# Inputs.net
KiCad netlist of a schematic drawn in Altium Designer
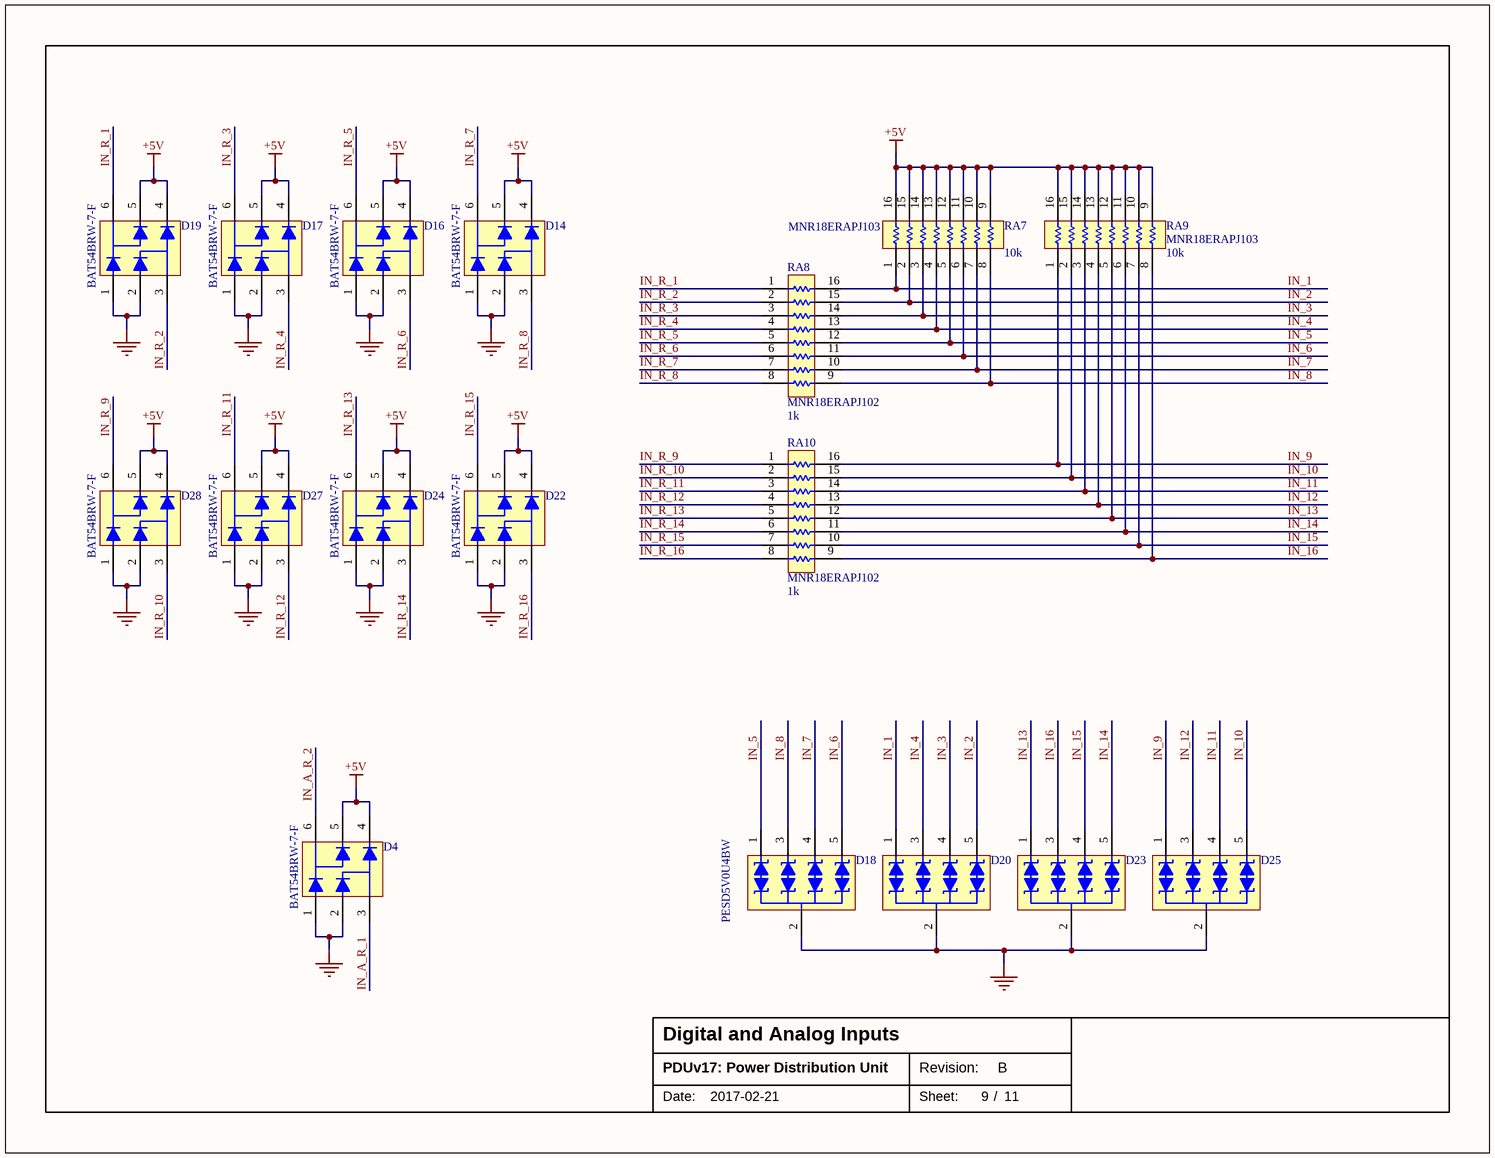
[diagram p0: Inputs.SchDoc]

(export (version "E")
  (design (tool "Eeschema 10.0.6"))
  (components
    (comp (ref "D4")
      (value "BAT54BRW-7-F")
      (footprint "SOT65P210X110-6N")
      (libsource (lib "PDU-UV17") (part "BAT54BRW-7-F"))
    )
    (comp (ref "D14")
      (value "BAT54BRW-7-F")
      (footprint "SOT65P210X110-6N")
      (libsource (lib "PDU-UV17") (part "BAT54BRW-7-F"))
    )
    (comp (ref "D16")
      (value "BAT54BRW-7-F")
      (footprint "SOT65P210X110-6N")
      (libsource (lib "PDU-UV17") (part "BAT54BRW-7-F"))
    )
    (comp (ref "D17")
      (value "BAT54BRW-7-F")
      (footprint "SOT65P210X110-6N")
      (libsource (lib "PDU-UV17") (part "BAT54BRW-7-F"))
    )
    (comp (ref "D18")
      (value "PESD5V0U4BW")
      (footprint "SOTFL50P160X60-5N")
      (libsource (lib "PDU-UV17") (part "PESD5V0U4BW"))
    )
    (comp (ref "D19")
      (value "BAT54BRW-7-F")
      (footprint "SOT65P210X110-6N")
      (libsource (lib "PDU-UV17") (part "BAT54BRW-7-F"))
    )
    (comp (ref "D20")
      (value "PESD5V0U4BW")
      (footprint "SOTFL50P160X60-5N")
      (libsource (lib "PDU-UV17") (part "PESD5V0U4BW"))
    )
    (comp (ref "D22")
      (value "BAT54BRW-7-F")
      (footprint "SOT65P210X110-6N")
      (libsource (lib "PDU-UV17") (part "BAT54BRW-7-F"))
    )
    (comp (ref "D23")
      (value "PESD5V0U4BW")
      (footprint "SOTFL50P160X60-5N")
      (libsource (lib "PDU-UV17") (part "PESD5V0U4BW"))
    )
    (comp (ref "D24")
      (value "BAT54BRW-7-F")
      (footprint "SOT65P210X110-6N")
      (libsource (lib "PDU-UV17") (part "BAT54BRW-7-F"))
    )
    (comp (ref "D25")
      (value "PESD5V0U4BW")
      (footprint "SOTFL50P160X60-5N")
      (libsource (lib "PDU-UV17") (part "PESD5V0U4BW"))
    )
    (comp (ref "D27")
      (value "BAT54BRW-7-F")
      (footprint "SOT65P210X110-6N")
      (libsource (lib "PDU-UV17") (part "BAT54BRW-7-F"))
    )
    (comp (ref "D28")
      (value "BAT54BRW-7-F")
      (footprint "SOT65P210X110-6N")
      (libsource (lib "PDU-UV17") (part "BAT54BRW-7-F"))
    )
    (comp (ref "RA7")
      (value "MNR18ERAPJ103")
      (footprint "CAC-50P379X150-16N")
      (fields (field (name "ALTIUM_VALUE") "10k"))
      (libsource (lib "PDU-UV17") (part "MNR18ERAPJ103"))
    )
    (comp (ref "RA8")
      (value "MNR18ERAPJ102")
      (footprint "CAC-50P379X150-16N")
      (fields (field (name "ALTIUM_VALUE") "1k"))
      (libsource (lib "PDU-UV17") (part "MNR18ERAPJ102"))
    )
    (comp (ref "RA9")
      (value "MNR18ERAPJ103")
      (footprint "CAC-50P379X150-16N")
      (fields (field (name "ALTIUM_VALUE") "10k"))
      (libsource (lib "PDU-UV17") (part "MNR18ERAPJ103"))
    )
    (comp (ref "RA10")
      (value "MNR18ERAPJ102")
      (footprint "CAC-50P379X150-16N")
      (fields (field (name "ALTIUM_VALUE") "1k"))
      (libsource (lib "PDU-UV17") (part "MNR18ERAPJ102"))
    )
  )
  (nets
    (net (code "1") (name "+5V") (class "Default")
      (node (ref "D14") (pin "4") (pinfunction "4_4") (pintype "passive"))
      (node (ref "D14") (pin "5") (pinfunction "5_5") (pintype "passive"))
      (node (ref "D16") (pin "4") (pinfunction "4_4") (pintype "passive"))
      (node (ref "D16") (pin "5") (pinfunction "5_5") (pintype "passive"))
      (node (ref "D17") (pin "4") (pinfunction "4_4") (pintype "passive"))
      (node (ref "D17") (pin "5") (pinfunction "5_5") (pintype "passive"))
      (node (ref "D19") (pin "4") (pinfunction "4_4") (pintype "passive"))
      (node (ref "D19") (pin "5") (pinfunction "5_5") (pintype "passive"))
      (node (ref "D22") (pin "4") (pinfunction "4_4") (pintype "passive"))
      (node (ref "D22") (pin "5") (pinfunction "5_5") (pintype "passive"))
      (node (ref "D24") (pin "4") (pinfunction "4_4") (pintype "passive"))
      (node (ref "D24") (pin "5") (pinfunction "5_5") (pintype "passive"))
      (node (ref "D27") (pin "4") (pinfunction "4_4") (pintype "passive"))
      (node (ref "D27") (pin "5") (pinfunction "5_5") (pintype "passive"))
      (node (ref "D28") (pin "4") (pinfunction "4_4") (pintype "passive"))
      (node (ref "D28") (pin "5") (pinfunction "5_5") (pintype "passive"))
      (node (ref "D4") (pin "4") (pinfunction "4_4") (pintype "passive"))
      (node (ref "D4") (pin "5") (pinfunction "5_5") (pintype "passive"))
      (node (ref "RA7") (pin "10") (pinfunction "10_10") (pintype "passive"))
      (node (ref "RA7") (pin "11") (pinfunction "11_11") (pintype "passive"))
      (node (ref "RA7") (pin "12") (pinfunction "12_12") (pintype "passive"))
      (node (ref "RA7") (pin "13") (pinfunction "13_13") (pintype "passive"))
      (node (ref "RA7") (pin "14") (pinfunction "14_14") (pintype "passive"))
      (node (ref "RA7") (pin "15") (pinfunction "15_15") (pintype "passive"))
      (node (ref "RA7") (pin "16") (pinfunction "16_16") (pintype "passive"))
      (node (ref "RA7") (pin "9") (pinfunction "9_9") (pintype "passive"))
      (node (ref "RA9") (pin "10") (pinfunction "10_10") (pintype "passive"))
      (node (ref "RA9") (pin "11") (pinfunction "11_11") (pintype "passive"))
      (node (ref "RA9") (pin "12") (pinfunction "12_12") (pintype "passive"))
      (node (ref "RA9") (pin "13") (pinfunction "13_13") (pintype "passive"))
      (node (ref "RA9") (pin "14") (pinfunction "14_14") (pintype "passive"))
      (node (ref "RA9") (pin "15") (pinfunction "15_15") (pintype "passive"))
      (node (ref "RA9") (pin "16") (pinfunction "16_16") (pintype "passive"))
      (node (ref "RA9") (pin "9") (pinfunction "9_9") (pintype "passive"))
    )
    (net (code "2") (name "/IN_1") (class "Default")
      (node (ref "D20") (pin "1") (pinfunction "1_1") (pintype "passive"))
      (node (ref "RA7") (pin "1") (pinfunction "1_1") (pintype "passive"))
      (node (ref "RA8") (pin "16") (pinfunction "16_16") (pintype "passive"))
    )
    (net (code "3") (name "/IN_2") (class "Default")
      (node (ref "D20") (pin "5") (pinfunction "5_5") (pintype "passive"))
      (node (ref "RA7") (pin "2") (pinfunction "2_2") (pintype "passive"))
      (node (ref "RA8") (pin "15") (pinfunction "15_15") (pintype "passive"))
    )
    (net (code "4") (name "/IN_3") (class "Default")
      (node (ref "D20") (pin "4") (pinfunction "4_4") (pintype "passive"))
      (node (ref "RA7") (pin "3") (pinfunction "3_3") (pintype "passive"))
      (node (ref "RA8") (pin "14") (pinfunction "14_14") (pintype "passive"))
    )
    (net (code "5") (name "/IN_4") (class "Default")
      (node (ref "D20") (pin "3") (pinfunction "3_3") (pintype "passive"))
      (node (ref "RA7") (pin "4") (pinfunction "4_4") (pintype "passive"))
      (node (ref "RA8") (pin "13") (pinfunction "13_13") (pintype "passive"))
    )
    (net (code "6") (name "/IN_5") (class "Default")
      (node (ref "D18") (pin "1") (pinfunction "1_1") (pintype "passive"))
      (node (ref "RA7") (pin "5") (pinfunction "5_5") (pintype "passive"))
      (node (ref "RA8") (pin "12") (pinfunction "12_12") (pintype "passive"))
    )
    (net (code "7") (name "/IN_6") (class "Default")
      (node (ref "D18") (pin "5") (pinfunction "5_5") (pintype "passive"))
      (node (ref "RA7") (pin "6") (pinfunction "6_6") (pintype "passive"))
      (node (ref "RA8") (pin "11") (pinfunction "11_11") (pintype "passive"))
    )
    (net (code "8") (name "/IN_7") (class "Default")
      (node (ref "D18") (pin "4") (pinfunction "4_4") (pintype "passive"))
      (node (ref "RA7") (pin "7") (pinfunction "7_7") (pintype "passive"))
      (node (ref "RA8") (pin "10") (pinfunction "10_10") (pintype "passive"))
    )
    (net (code "9") (name "/IN_8") (class "Default")
      (node (ref "D18") (pin "3") (pinfunction "3_3") (pintype "passive"))
      (node (ref "RA7") (pin "8") (pinfunction "8_8") (pintype "passive"))
      (node (ref "RA8") (pin "9") (pinfunction "9_9") (pintype "passive"))
    )
    (net (code "10") (name "/IN_9") (class "Default")
      (node (ref "D25") (pin "1") (pinfunction "1_1") (pintype "passive"))
      (node (ref "RA10") (pin "16") (pinfunction "16_16") (pintype "passive"))
      (node (ref "RA9") (pin "1") (pinfunction "1_1") (pintype "passive"))
    )
    (net (code "11") (name "/IN_10") (class "Default")
      (node (ref "D25") (pin "5") (pinfunction "5_5") (pintype "passive"))
      (node (ref "RA10") (pin "15") (pinfunction "15_15") (pintype "passive"))
      (node (ref "RA9") (pin "2") (pinfunction "2_2") (pintype "passive"))
    )
    (net (code "12") (name "/IN_11") (class "Default")
      (node (ref "D25") (pin "4") (pinfunction "4_4") (pintype "passive"))
      (node (ref "RA10") (pin "14") (pinfunction "14_14") (pintype "passive"))
      (node (ref "RA9") (pin "3") (pinfunction "3_3") (pintype "passive"))
    )
    (net (code "13") (name "/IN_12") (class "Default")
      (node (ref "D25") (pin "3") (pinfunction "3_3") (pintype "passive"))
      (node (ref "RA10") (pin "13") (pinfunction "13_13") (pintype "passive"))
      (node (ref "RA9") (pin "4") (pinfunction "4_4") (pintype "passive"))
    )
    (net (code "14") (name "/IN_13") (class "Default")
      (node (ref "D23") (pin "1") (pinfunction "1_1") (pintype "passive"))
      (node (ref "RA10") (pin "12") (pinfunction "12_12") (pintype "passive"))
      (node (ref "RA9") (pin "5") (pinfunction "5_5") (pintype "passive"))
    )
    (net (code "15") (name "/IN_14") (class "Default")
      (node (ref "D23") (pin "5") (pinfunction "5_5") (pintype "passive"))
      (node (ref "RA10") (pin "11") (pinfunction "11_11") (pintype "passive"))
      (node (ref "RA9") (pin "6") (pinfunction "6_6") (pintype "passive"))
    )
    (net (code "16") (name "/IN_15") (class "Default")
      (node (ref "D23") (pin "4") (pinfunction "4_4") (pintype "passive"))
      (node (ref "RA10") (pin "10") (pinfunction "10_10") (pintype "passive"))
      (node (ref "RA9") (pin "7") (pinfunction "7_7") (pintype "passive"))
    )
    (net (code "17") (name "/IN_16") (class "Default")
      (node (ref "D23") (pin "3") (pinfunction "3_3") (pintype "passive"))
      (node (ref "RA10") (pin "9") (pinfunction "9_9") (pintype "passive"))
      (node (ref "RA9") (pin "8") (pinfunction "8_8") (pintype "passive"))
    )
    (net (code "18") (name "/IN_A_R_1") (class "Default")
      (node (ref "D4") (pin "3") (pinfunction "3_3") (pintype "passive"))
    )
    (net (code "19") (name "/IN_A_R_2") (class "Default")
      (node (ref "D4") (pin "6") (pinfunction "6_6") (pintype "passive"))
    )
    (net (code "20") (name "/IN_R_1") (class "Default")
      (node (ref "D19") (pin "6") (pinfunction "6_6") (pintype "passive"))
      (node (ref "RA8") (pin "1") (pinfunction "1_1") (pintype "passive"))
    )
    (net (code "21") (name "/IN_R_2") (class "Default")
      (node (ref "D19") (pin "3") (pinfunction "3_3") (pintype "passive"))
      (node (ref "RA8") (pin "2") (pinfunction "2_2") (pintype "passive"))
    )
    (net (code "22") (name "/IN_R_3") (class "Default")
      (node (ref "D17") (pin "6") (pinfunction "6_6") (pintype "passive"))
      (node (ref "RA8") (pin "3") (pinfunction "3_3") (pintype "passive"))
    )
    (net (code "23") (name "/IN_R_4") (class "Default")
      (node (ref "D17") (pin "3") (pinfunction "3_3") (pintype "passive"))
      (node (ref "RA8") (pin "4") (pinfunction "4_4") (pintype "passive"))
    )
    (net (code "24") (name "/IN_R_5") (class "Default")
      (node (ref "D16") (pin "6") (pinfunction "6_6") (pintype "passive"))
      (node (ref "RA8") (pin "5") (pinfunction "5_5") (pintype "passive"))
    )
    (net (code "25") (name "/IN_R_6") (class "Default")
      (node (ref "D16") (pin "3") (pinfunction "3_3") (pintype "passive"))
      (node (ref "RA8") (pin "6") (pinfunction "6_6") (pintype "passive"))
    )
    (net (code "26") (name "/IN_R_7") (class "Default")
      (node (ref "D14") (pin "6") (pinfunction "6_6") (pintype "passive"))
      (node (ref "RA8") (pin "7") (pinfunction "7_7") (pintype "passive"))
    )
    (net (code "27") (name "/IN_R_8") (class "Default")
      (node (ref "D14") (pin "3") (pinfunction "3_3") (pintype "passive"))
      (node (ref "RA8") (pin "8") (pinfunction "8_8") (pintype "passive"))
    )
    (net (code "28") (name "/IN_R_9") (class "Default")
      (node (ref "D28") (pin "6") (pinfunction "6_6") (pintype "passive"))
      (node (ref "RA10") (pin "1") (pinfunction "1_1") (pintype "passive"))
    )
    (net (code "29") (name "/IN_R_10") (class "Default")
      (node (ref "D28") (pin "3") (pinfunction "3_3") (pintype "passive"))
      (node (ref "RA10") (pin "2") (pinfunction "2_2") (pintype "passive"))
    )
    (net (code "30") (name "/IN_R_11") (class "Default")
      (node (ref "D27") (pin "6") (pinfunction "6_6") (pintype "passive"))
      (node (ref "RA10") (pin "3") (pinfunction "3_3") (pintype "passive"))
    )
    (net (code "31") (name "/IN_R_12") (class "Default")
      (node (ref "D27") (pin "3") (pinfunction "3_3") (pintype "passive"))
      (node (ref "RA10") (pin "4") (pinfunction "4_4") (pintype "passive"))
    )
    (net (code "32") (name "/IN_R_13") (class "Default")
      (node (ref "D24") (pin "6") (pinfunction "6_6") (pintype "passive"))
      (node (ref "RA10") (pin "5") (pinfunction "5_5") (pintype "passive"))
    )
    (net (code "33") (name "/IN_R_14") (class "Default")
      (node (ref "D24") (pin "3") (pinfunction "3_3") (pintype "passive"))
      (node (ref "RA10") (pin "6") (pinfunction "6_6") (pintype "passive"))
    )
    (net (code "34") (name "/IN_R_15") (class "Default")
      (node (ref "D22") (pin "6") (pinfunction "6_6") (pintype "passive"))
      (node (ref "RA10") (pin "7") (pinfunction "7_7") (pintype "passive"))
    )
    (net (code "35") (name "/IN_R_16") (class "Default")
      (node (ref "D22") (pin "3") (pinfunction "3_3") (pintype "passive"))
      (node (ref "RA10") (pin "8") (pinfunction "8_8") (pintype "passive"))
    )
    (net (code "36") (name "GND") (class "Default")
      (node (ref "D14") (pin "1") (pinfunction "1_1") (pintype "passive"))
      (node (ref "D14") (pin "2") (pinfunction "2_2") (pintype "passive"))
      (node (ref "D16") (pin "1") (pinfunction "1_1") (pintype "passive"))
      (node (ref "D16") (pin "2") (pinfunction "2_2") (pintype "passive"))
      (node (ref "D17") (pin "1") (pinfunction "1_1") (pintype "passive"))
      (node (ref "D17") (pin "2") (pinfunction "2_2") (pintype "passive"))
      (node (ref "D18") (pin "2") (pinfunction "2_2") (pintype "passive"))
      (node (ref "D19") (pin "1") (pinfunction "1_1") (pintype "passive"))
      (node (ref "D19") (pin "2") (pinfunction "2_2") (pintype "passive"))
      (node (ref "D20") (pin "2") (pinfunction "2_2") (pintype "passive"))
      (node (ref "D22") (pin "1") (pinfunction "1_1") (pintype "passive"))
      (node (ref "D22") (pin "2") (pinfunction "2_2") (pintype "passive"))
      (node (ref "D23") (pin "2") (pinfunction "2_2") (pintype "passive"))
      (node (ref "D24") (pin "1") (pinfunction "1_1") (pintype "passive"))
      (node (ref "D24") (pin "2") (pinfunction "2_2") (pintype "passive"))
      (node (ref "D25") (pin "2") (pinfunction "2_2") (pintype "passive"))
      (node (ref "D27") (pin "1") (pinfunction "1_1") (pintype "passive"))
      (node (ref "D27") (pin "2") (pinfunction "2_2") (pintype "passive"))
      (node (ref "D28") (pin "1") (pinfunction "1_1") (pintype "passive"))
      (node (ref "D28") (pin "2") (pinfunction "2_2") (pintype "passive"))
      (node (ref "D4") (pin "1") (pinfunction "1_1") (pintype "passive"))
      (node (ref "D4") (pin "2") (pinfunction "2_2") (pintype "passive"))
    )
  )
)
